# ConverterBoard.net
KiCad netlist of a schematic drawn in EAGLE
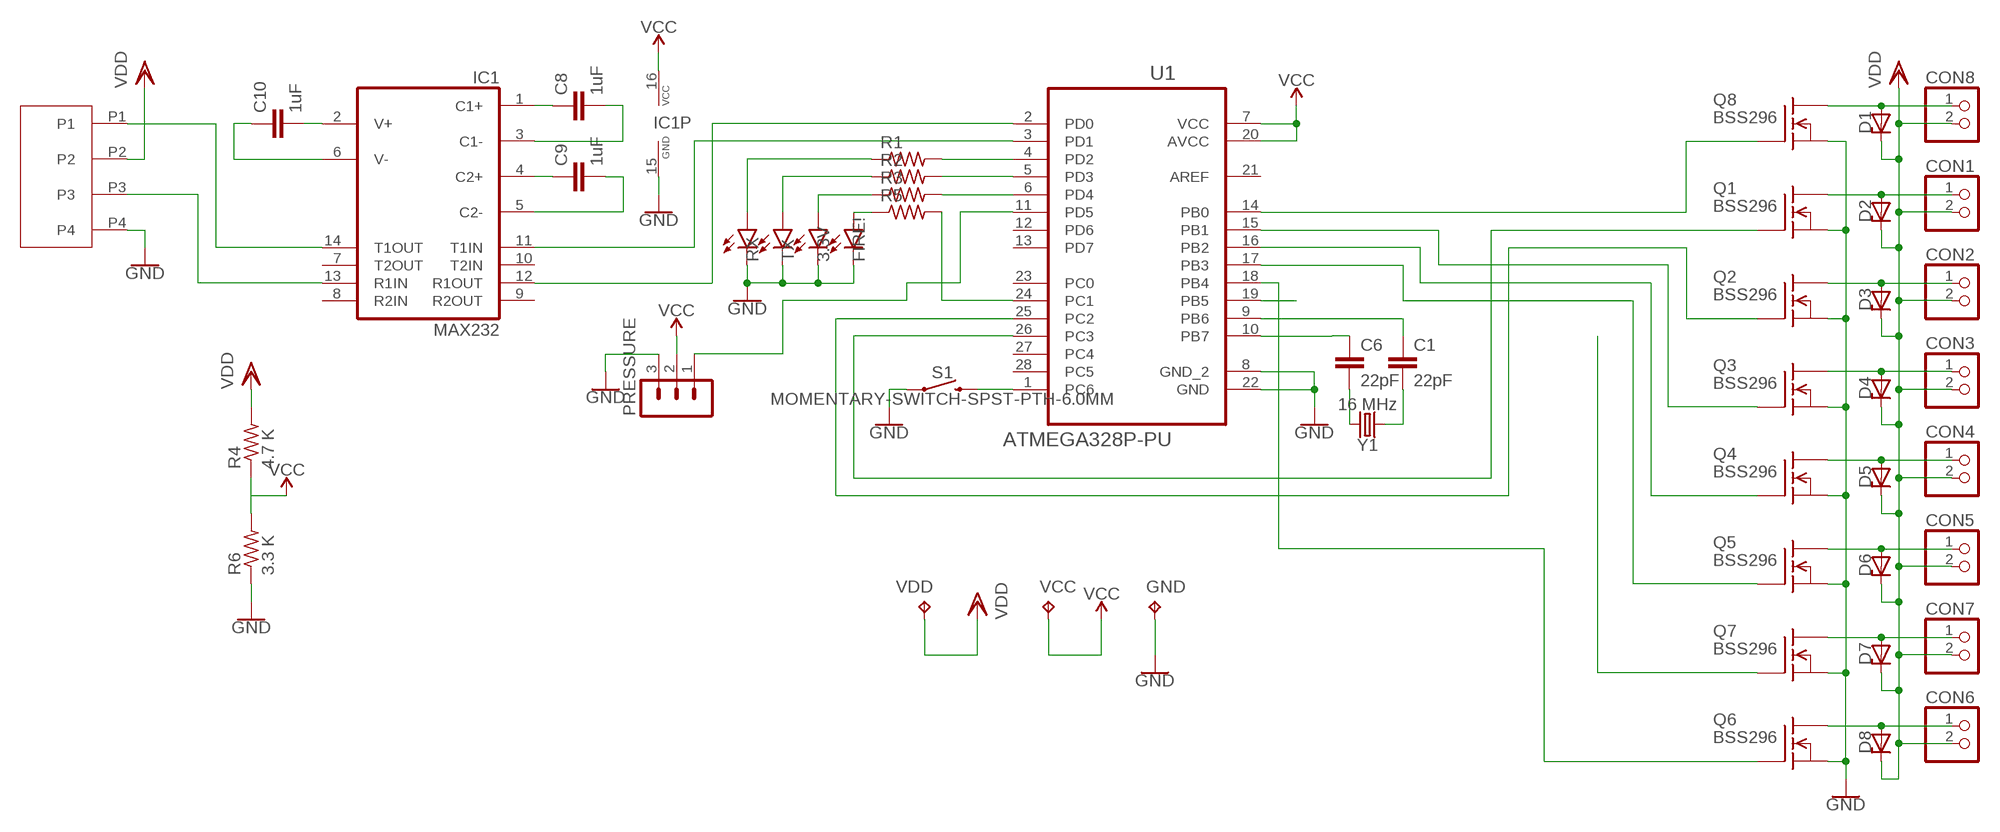
[diagram p0: schematic, sheet 1]

(export (version "E")
  (design (tool "Eeschema 10.0.6"))
  (components
    (comp (ref "3.3V")
      (value "BLUE")
      (footprint "eagle-import:LED-0603")
      (libsource (lib "eagle-import") (part "LED-BLUE0603"))
    )
    (comp (ref "C1")
      (value "22pF")
      (footprint "eagle-import:0603")
      (libsource (lib "eagle-import") (part "470PF-0603-50V-5%"))
    )
    (comp (ref "C6")
      (value "22pF")
      (footprint "eagle-import:0603")
      (libsource (lib "eagle-import") (part "470PF-0603-50V-5%"))
    )
    (comp (ref "C8")
      (value "1uF")
      (footprint "eagle-import:0603")
      (libsource (lib "eagle-import") (part "470PF-0603-50V-5%"))
    )
    (comp (ref "C9")
      (value "1uF")
      (footprint "eagle-import:0603")
      (libsource (lib "eagle-import") (part "470PF-0603-50V-5%"))
    )
    (comp (ref "C10")
      (value "1uF")
      (footprint "eagle-import:0603")
      (libsource (lib "eagle-import") (part "470PF-0603-50V-5%"))
    )
    (comp (ref "CON1")
      (value "PINHD-1X2")
      (footprint "eagle-import:1X02")
      (libsource (lib "eagle-import") (part "PINHD-1X2"))
    )
    (comp (ref "CON2")
      (value "PINHD-1X2")
      (footprint "eagle-import:1X02")
      (libsource (lib "eagle-import") (part "PINHD-1X2"))
    )
    (comp (ref "CON3")
      (value "PINHD-1X2")
      (footprint "eagle-import:1X02")
      (libsource (lib "eagle-import") (part "PINHD-1X2"))
    )
    (comp (ref "CON4")
      (value "PINHD-1X2")
      (footprint "eagle-import:1X02")
      (libsource (lib "eagle-import") (part "PINHD-1X2"))
    )
    (comp (ref "CON5")
      (value "PINHD-1X2")
      (footprint "eagle-import:1X02")
      (libsource (lib "eagle-import") (part "PINHD-1X2"))
    )
    (comp (ref "CON6")
      (value "PINHD-1X2")
      (footprint "eagle-import:1X02")
      (libsource (lib "eagle-import") (part "PINHD-1X2"))
    )
    (comp (ref "CON7")
      (value "PINHD-1X2")
      (footprint "eagle-import:1X02")
      (libsource (lib "eagle-import") (part "PINHD-1X2"))
    )
    (comp (ref "CON8")
      (value "PINHD-1X2")
      (footprint "eagle-import:1X02")
      (libsource (lib "eagle-import") (part "PINHD-1X2"))
    )
    (comp (ref "D1")
      (value "BZX90")
      (footprint "eagle-import:DO34Z7")
      (libsource (lib "eagle-import") (part "BZX90"))
    )
    (comp (ref "D2")
      (value "BZX90")
      (footprint "eagle-import:DO34Z7")
      (libsource (lib "eagle-import") (part "BZX90"))
    )
    (comp (ref "D3")
      (value "BZX90")
      (footprint "eagle-import:DO34Z7")
      (libsource (lib "eagle-import") (part "BZX90"))
    )
    (comp (ref "D4")
      (value "BZX90")
      (footprint "eagle-import:DO34Z7")
      (libsource (lib "eagle-import") (part "BZX90"))
    )
    (comp (ref "D5")
      (value "BZX90")
      (footprint "eagle-import:DO34Z7")
      (libsource (lib "eagle-import") (part "BZX90"))
    )
    (comp (ref "D6")
      (value "BZX90")
      (footprint "eagle-import:DO34Z7")
      (libsource (lib "eagle-import") (part "BZX90"))
    )
    (comp (ref "D7")
      (value "BZX90")
      (footprint "eagle-import:DO34Z7")
      (libsource (lib "eagle-import") (part "BZX90"))
    )
    (comp (ref "D8")
      (value "BZX90")
      (footprint "eagle-import:DO34Z7")
      (libsource (lib "eagle-import") (part "BZX90"))
    )
    (comp (ref "FIRE!")
      (value "BLUE")
      (footprint "eagle-import:LED-0603")
      (libsource (lib "eagle-import") (part "LED-BLUE0603"))
    )
    (comp (ref "GND")
      (value "TPTP11R")
      (footprint "eagle-import:TP11R")
      (libsource (lib "eagle-import") (part "TPTP11R"))
    )
    (comp (ref "IC1")
      (value "MAX232")
      (footprint "eagle-import:DIL16")
      (fields (field (name "MF") "MAXIM") (field (name "MPN") "MAX232ACPE+"))
      (libsource (lib "eagle-import") (part "MAX232"))
    )
    (comp (ref "PRESSURE")
      (value "MA03-1")
      (footprint "eagle-import:MA03-1")
      (libsource (lib "eagle-import") (part "MA03-1"))
    )
    (comp (ref "Q1")
      (value "BSS296")
      (footprint "eagle-import:TO92")
      (libsource (lib "eagle-import") (part "BSS296"))
    )
    (comp (ref "Q2")
      (value "BSS296")
      (footprint "eagle-import:TO92")
      (libsource (lib "eagle-import") (part "BSS296"))
    )
    (comp (ref "Q3")
      (value "BSS296")
      (footprint "eagle-import:TO92")
      (libsource (lib "eagle-import") (part "BSS296"))
    )
    (comp (ref "Q4")
      (value "BSS296")
      (footprint "eagle-import:TO92")
      (libsource (lib "eagle-import") (part "BSS296"))
    )
    (comp (ref "Q5")
      (value "BSS296")
      (footprint "eagle-import:TO92")
      (libsource (lib "eagle-import") (part "BSS296"))
    )
    (comp (ref "Q6")
      (value "BSS296")
      (footprint "eagle-import:TO92")
      (libsource (lib "eagle-import") (part "BSS296"))
    )
    (comp (ref "Q7")
      (value "BSS296")
      (footprint "eagle-import:TO92")
      (libsource (lib "eagle-import") (part "BSS296"))
    )
    (comp (ref "Q8")
      (value "BSS296")
      (footprint "eagle-import:TO92")
      (libsource (lib "eagle-import") (part "BSS296"))
    )
    (comp (ref "R1")
      (value "R-US_0204/2V")
      (footprint "eagle-import:0204V")
      (libsource (lib "eagle-import") (part "R-US_0204/2V"))
    )
    (comp (ref "R2")
      (value "R-US_0204/2V")
      (footprint "eagle-import:0204V")
      (libsource (lib "eagle-import") (part "R-US_0204/2V"))
    )
    (comp (ref "R3")
      (value "R-US_0204/2V")
      (footprint "eagle-import:0204V")
      (libsource (lib "eagle-import") (part "R-US_0204/2V"))
    )
    (comp (ref "R4")
      (value "4.7 K")
      (footprint "eagle-import:0204V")
      (libsource (lib "eagle-import") (part "R-US_0204/2V"))
    )
    (comp (ref "R5")
      (value "R-US_0204/2V")
      (footprint "eagle-import:0204V")
      (libsource (lib "eagle-import") (part "R-US_0204/2V"))
    )
    (comp (ref "R6")
      (value "3.3 K")
      (footprint "eagle-import:0204V")
      (libsource (lib "eagle-import") (part "R-US_0204/2V"))
    )
    (comp (ref "RX")
      (value "BLUE")
      (footprint "eagle-import:LED-0603")
      (libsource (lib "eagle-import") (part "LED-BLUE0603"))
    )
    (comp (ref "S1")
      (value "MOMENTARY-SWITCH-SPST-PTH-6.0MM")
      (footprint "eagle-import:TACTILE_SWITCH_PTH_6.0MM")
      (libsource (lib "eagle-import") (part "MOMENTARY-SWITCH-SPST-PTH-6.0MM"))
    )
    (comp (ref "TX")
      (value "BLUE")
      (footprint "eagle-import:LED-0603")
      (libsource (lib "eagle-import") (part "LED-BLUE0603"))
    )
    (comp (ref "U$2")
      (value "MINI_FIT_JR_4PIN_VERT")
      (footprint "eagle-import:MINI_FIT_JR_4PIN_VERT")
      (libsource (lib "eagle-import") (part "MINI_FIT_JR_4PIN_VERT"))
    )
    (comp (ref "U1")
      (value "ATMEGA328P-PU")
      (footprint "eagle-import:DIP254P762X457-28")
      (libsource (lib "eagle-import") (part "ATMEGA328P-PU"))
    )
    (comp (ref "VCC")
      (value "TPTP11R")
      (footprint "eagle-import:TP11R")
      (libsource (lib "eagle-import") (part "TPTP11R"))
    )
    (comp (ref "VDD")
      (value "TPTP11R")
      (footprint "eagle-import:TP11R")
      (libsource (lib "eagle-import") (part "TPTP11R"))
    )
    (comp (ref "Y1")
      (value "16 MHz")
      (footprint "eagle-import:HC49U")
      (libsource (lib "eagle-import") (part "CRYSTALPTH-HC49UV"))
    )
  )
  (nets
    (net (code "1") (name "/Q7") (class "Default")
      (node (ref "Q7") (pin "1") (pinfunction "G_1") (pintype "passive"))
      (node (ref "U1") (pin "19") (pinfunction "PB5_19") (pintype "bidirectional"))
    )
    (net (code "2") (name "GND") (class "Default")
      (node (ref "3.3V") (pin "C") (pinfunction "C_C") (pintype "passive"))
      (node (ref "FIRE!") (pin "C") (pinfunction "C_C") (pintype "passive"))
      (node (ref "GND") (pin "TP") (pinfunction "TP_TP") (pintype "input"))
      (node (ref "IC1") (pin "15") (pinfunction "GND_15") (pintype "power_in"))
      (node (ref "PRESSURE") (pin "3") (pinfunction "3_3") (pintype "passive"))
      (node (ref "Q1") (pin "3") (pinfunction "S_3") (pintype "passive"))
      (node (ref "Q2") (pin "3") (pinfunction "S_3") (pintype "passive"))
      (node (ref "Q3") (pin "3") (pinfunction "S_3") (pintype "passive"))
      (node (ref "Q4") (pin "3") (pinfunction "S_3") (pintype "passive"))
      (node (ref "Q5") (pin "3") (pinfunction "S_3") (pintype "passive"))
      (node (ref "Q6") (pin "3") (pinfunction "S_3") (pintype "passive"))
      (node (ref "Q7") (pin "3") (pinfunction "S_3") (pintype "passive"))
      (node (ref "Q8") (pin "3") (pinfunction "S_3") (pintype "passive"))
      (node (ref "R6") (pin "1") (pinfunction "1_1") (pintype "passive"))
      (node (ref "RX") (pin "C") (pinfunction "C_C") (pintype "passive"))
      (node (ref "S1") (pin "1") (pinfunction "1_1") (pintype "passive"))
      (node (ref "TX") (pin "C") (pinfunction "C_C") (pintype "passive"))
      (node (ref "U$2") (pin "P4") (pinfunction "P4_P4") (pintype "bidirectional"))
      (node (ref "U1") (pin "22") (pinfunction "GND_22") (pintype "passive"))
      (node (ref "U1") (pin "8") (pinfunction "GND_2_8") (pintype "passive"))
    )
    (net (code "3") (name "Net-(3.3V-PadA)") (class "Default")
      (node (ref "3.3V") (pin "A") (pinfunction "A_A") (pintype "passive"))
      (node (ref "R3") (pin "1") (pinfunction "1_1") (pintype "passive"))
    )
    (net (code "4") (name "Net-(C1-Pad2)") (class "Default")
      (node (ref "C1") (pin "2") (pinfunction "2_2") (pintype "passive"))
      (node (ref "Y1") (pin "1") (pinfunction "1_1") (pintype "passive"))
    )
    (net (code "5") (name "Net-(C6-Pad2)") (class "Default")
      (node (ref "C6") (pin "2") (pinfunction "2_2") (pintype "passive"))
      (node (ref "Y1") (pin "2") (pinfunction "2_2") (pintype "passive"))
    )
    (net (code "6") (name "Net-(FIRE!-PadA)") (class "Default")
      (node (ref "FIRE!") (pin "A") (pinfunction "A_A") (pintype "passive"))
      (node (ref "R5") (pin "1") (pinfunction "1_1") (pintype "passive"))
    )
    (net (code "7") (name "Net-(IC1A-C1+)") (class "Default")
      (node (ref "C8") (pin "1") (pinfunction "1_1") (pintype "passive"))
      (node (ref "IC1") (pin "1") (pinfunction "C1+_1") (pintype "bidirectional"))
    )
    (net (code "8") (name "Net-(IC1A-C1-)") (class "Default")
      (node (ref "C8") (pin "2") (pinfunction "2_2") (pintype "passive"))
      (node (ref "IC1") (pin "3") (pinfunction "C1-_3") (pintype "bidirectional"))
    )
    (net (code "9") (name "Net-(IC1A-C2+)") (class "Default")
      (node (ref "C9") (pin "1") (pinfunction "1_1") (pintype "passive"))
      (node (ref "IC1") (pin "4") (pinfunction "C2+_4") (pintype "bidirectional"))
    )
    (net (code "10") (name "Net-(IC1A-C2-)") (class "Default")
      (node (ref "C9") (pin "2") (pinfunction "2_2") (pintype "passive"))
      (node (ref "IC1") (pin "5") (pinfunction "C2-_5") (pintype "bidirectional"))
    )
    (net (code "11") (name "Net-(IC1A-R1IN)") (class "Default")
      (node (ref "IC1") (pin "13") (pinfunction "R1IN_13") (pintype "input"))
      (node (ref "U$2") (pin "P3") (pinfunction "P3_P3") (pintype "bidirectional"))
    )
    (net (code "12") (name "Net-(IC1A-R1OUT)") (class "Default")
      (node (ref "IC1") (pin "12") (pinfunction "R1OUT_12") (pintype "output"))
      (node (ref "U1") (pin "2") (pinfunction "PD0_2") (pintype "bidirectional"))
    )
    (net (code "13") (name "Net-(IC1A-T1IN)") (class "Default")
      (node (ref "IC1") (pin "11") (pinfunction "T1IN_11") (pintype "input"))
      (node (ref "U1") (pin "3") (pinfunction "PD1_3") (pintype "bidirectional"))
    )
    (net (code "14") (name "Net-(IC1A-T1OUT)") (class "Default")
      (node (ref "IC1") (pin "14") (pinfunction "T1OUT_14") (pintype "output"))
      (node (ref "U$2") (pin "P1") (pinfunction "P1_P1") (pintype "bidirectional"))
    )
    (net (code "15") (name "Net-(IC1A-V+)") (class "Default")
      (node (ref "C10") (pin "2") (pinfunction "2_2") (pintype "passive"))
      (node (ref "IC1") (pin "2") (pinfunction "V+_2") (pintype "bidirectional"))
    )
    (net (code "16") (name "Net-(IC1A-V-)") (class "Default")
      (node (ref "C10") (pin "1") (pinfunction "1_1") (pintype "passive"))
      (node (ref "IC1") (pin "6") (pinfunction "V-_6") (pintype "bidirectional"))
    )
    (net (code "17") (name "Net-(Q1-D)") (class "Default")
      (node (ref "CON1") (pin "1") (pinfunction "1_1") (pintype "passive"))
      (node (ref "D2") (pin "A") (pinfunction "A_A") (pintype "passive"))
      (node (ref "Q1") (pin "2") (pinfunction "D_2") (pintype "passive"))
    )
    (net (code "18") (name "Net-(Q1-G)") (class "Default")
      (node (ref "Q1") (pin "1") (pinfunction "G_1") (pintype "passive"))
      (node (ref "U1") (pin "26") (pinfunction "PC3_26") (pintype "bidirectional"))
    )
    (net (code "19") (name "Net-(Q2-D)") (class "Default")
      (node (ref "CON2") (pin "1") (pinfunction "1_1") (pintype "passive"))
      (node (ref "D3") (pin "A") (pinfunction "A_A") (pintype "passive"))
      (node (ref "Q2") (pin "2") (pinfunction "D_2") (pintype "passive"))
    )
    (net (code "20") (name "Net-(Q2-G)") (class "Default")
      (node (ref "Q2") (pin "1") (pinfunction "G_1") (pintype "passive"))
      (node (ref "U1") (pin "25") (pinfunction "PC2_25") (pintype "bidirectional"))
    )
    (net (code "21") (name "Net-(Q3-D)") (class "Default")
      (node (ref "CON3") (pin "1") (pinfunction "1_1") (pintype "passive"))
      (node (ref "D4") (pin "A") (pinfunction "A_A") (pintype "passive"))
      (node (ref "Q3") (pin "2") (pinfunction "D_2") (pintype "passive"))
    )
    (net (code "22") (name "Net-(Q3-G)") (class "Default")
      (node (ref "Q3") (pin "1") (pinfunction "G_1") (pintype "passive"))
      (node (ref "U1") (pin "15") (pinfunction "PB1_15") (pintype "bidirectional"))
    )
    (net (code "23") (name "Net-(Q4-D)") (class "Default")
      (node (ref "CON4") (pin "1") (pinfunction "1_1") (pintype "passive"))
      (node (ref "D5") (pin "A") (pinfunction "A_A") (pintype "passive"))
      (node (ref "Q4") (pin "2") (pinfunction "D_2") (pintype "passive"))
    )
    (net (code "24") (name "Net-(Q4-G)") (class "Default")
      (node (ref "Q4") (pin "1") (pinfunction "G_1") (pintype "passive"))
      (node (ref "U1") (pin "16") (pinfunction "PB2_16") (pintype "bidirectional"))
    )
    (net (code "25") (name "Net-(Q5-D)") (class "Default")
      (node (ref "CON5") (pin "1") (pinfunction "1_1") (pintype "passive"))
      (node (ref "D6") (pin "A") (pinfunction "A_A") (pintype "passive"))
      (node (ref "Q5") (pin "2") (pinfunction "D_2") (pintype "passive"))
    )
    (net (code "26") (name "Net-(Q5-G)") (class "Default")
      (node (ref "Q5") (pin "1") (pinfunction "G_1") (pintype "passive"))
      (node (ref "U1") (pin "17") (pinfunction "PB3_17") (pintype "bidirectional"))
    )
    (net (code "27") (name "Net-(Q6-D)") (class "Default")
      (node (ref "CON6") (pin "1") (pinfunction "1_1") (pintype "passive"))
      (node (ref "D8") (pin "A") (pinfunction "A_A") (pintype "passive"))
      (node (ref "Q6") (pin "2") (pinfunction "D_2") (pintype "passive"))
    )
    (net (code "28") (name "Net-(Q6-G)") (class "Default")
      (node (ref "Q6") (pin "1") (pinfunction "G_1") (pintype "passive"))
      (node (ref "U1") (pin "18") (pinfunction "PB4_18") (pintype "bidirectional"))
    )
    (net (code "29") (name "Net-(Q7-D)") (class "Default")
      (node (ref "CON7") (pin "1") (pinfunction "1_1") (pintype "passive"))
      (node (ref "D7") (pin "A") (pinfunction "A_A") (pintype "passive"))
      (node (ref "Q7") (pin "2") (pinfunction "D_2") (pintype "passive"))
    )
    (net (code "30") (name "Net-(Q8-D)") (class "Default")
      (node (ref "CON8") (pin "1") (pinfunction "1_1") (pintype "passive"))
      (node (ref "D1") (pin "A") (pinfunction "A_A") (pintype "passive"))
      (node (ref "Q8") (pin "2") (pinfunction "D_2") (pintype "passive"))
    )
    (net (code "31") (name "Net-(Q8-G)") (class "Default")
      (node (ref "Q8") (pin "1") (pinfunction "G_1") (pintype "passive"))
      (node (ref "U1") (pin "14") (pinfunction "PB0_14") (pintype "bidirectional"))
    )
    (net (code "32") (name "Net-(R1-Pad1)") (class "Default")
      (node (ref "R1") (pin "1") (pinfunction "1_1") (pintype "passive"))
      (node (ref "RX") (pin "A") (pinfunction "A_A") (pintype "passive"))
    )
    (net (code "33") (name "Net-(R2-Pad1)") (class "Default")
      (node (ref "R2") (pin "1") (pinfunction "1_1") (pintype "passive"))
      (node (ref "TX") (pin "A") (pinfunction "A_A") (pintype "passive"))
    )
    (net (code "34") (name "Net-(R4-Pad1)") (class "Default")
      (node (ref "R4") (pin "1") (pinfunction "1_1") (pintype "passive"))
      (node (ref "R6") (pin "2") (pinfunction "2_2") (pintype "passive"))
    )
    (net (code "35") (name "Net-(S1-2)") (class "Default")
      (node (ref "S1") (pin "3") (pinfunction "2_3") (pintype "passive"))
      (node (ref "U1") (pin "1") (pinfunction "PC6_1") (pintype "bidirectional"))
    )
    (net (code "36") (name "Net-(U1-PB6)") (class "Default")
      (node (ref "C1") (pin "1") (pinfunction "1_1") (pintype "passive"))
      (node (ref "U1") (pin "9") (pinfunction "PB6_9") (pintype "bidirectional"))
    )
    (net (code "37") (name "Net-(U1-PB7)") (class "Default")
      (node (ref "C6") (pin "1") (pinfunction "1_1") (pintype "passive"))
      (node (ref "U1") (pin "10") (pinfunction "PB7_10") (pintype "bidirectional"))
    )
    (net (code "38") (name "Net-(U1-PC1)") (class "Default")
      (node (ref "R5") (pin "2") (pinfunction "2_2") (pintype "passive"))
      (node (ref "U1") (pin "24") (pinfunction "PC1_24") (pintype "bidirectional"))
    )
    (net (code "39") (name "Net-(U1-PD2)") (class "Default")
      (node (ref "R1") (pin "2") (pinfunction "2_2") (pintype "passive"))
      (node (ref "U1") (pin "4") (pinfunction "PD2_4") (pintype "bidirectional"))
    )
    (net (code "40") (name "Net-(U1-PD3)") (class "Default")
      (node (ref "R2") (pin "2") (pinfunction "2_2") (pintype "passive"))
      (node (ref "U1") (pin "5") (pinfunction "PD3_5") (pintype "bidirectional"))
    )
    (net (code "41") (name "Net-(U1-PD4)") (class "Default")
      (node (ref "R3") (pin "2") (pinfunction "2_2") (pintype "passive"))
      (node (ref "U1") (pin "6") (pinfunction "PD4_6") (pintype "bidirectional"))
    )
    (net (code "42") (name "Net-(U1-PD5)") (class "Default")
      (node (ref "PRESSURE") (pin "1") (pinfunction "1_1") (pintype "passive"))
      (node (ref "U1") (pin "11") (pinfunction "PD5_11") (pintype "bidirectional"))
    )
    (net (code "43") (name "VCC") (class "Default")
      (node (ref "IC1") (pin "16") (pinfunction "VCC_16") (pintype "power_in"))
      (node (ref "PRESSURE") (pin "2") (pinfunction "2_2") (pintype "passive"))
      (node (ref "U1") (pin "20") (pinfunction "AVCC_20") (pintype "power_in"))
      (node (ref "U1") (pin "7") (pinfunction "VCC_7") (pintype "power_in"))
      (node (ref "VCC") (pin "TP") (pinfunction "TP_TP") (pintype "input"))
    )
    (net (code "44") (name "VDD") (class "Default")
      (node (ref "CON1") (pin "2") (pinfunction "2_2") (pintype "passive"))
      (node (ref "CON2") (pin "2") (pinfunction "2_2") (pintype "passive"))
      (node (ref "CON3") (pin "2") (pinfunction "2_2") (pintype "passive"))
      (node (ref "CON4") (pin "2") (pinfunction "2_2") (pintype "passive"))
      (node (ref "CON5") (pin "2") (pinfunction "2_2") (pintype "passive"))
      (node (ref "CON6") (pin "2") (pinfunction "2_2") (pintype "passive"))
      (node (ref "CON7") (pin "2") (pinfunction "2_2") (pintype "passive"))
      (node (ref "CON8") (pin "2") (pinfunction "2_2") (pintype "passive"))
      (node (ref "D1") (pin "C") (pinfunction "C_C") (pintype "passive"))
      (node (ref "D2") (pin "C") (pinfunction "C_C") (pintype "passive"))
      (node (ref "D3") (pin "C") (pinfunction "C_C") (pintype "passive"))
      (node (ref "D4") (pin "C") (pinfunction "C_C") (pintype "passive"))
      (node (ref "D5") (pin "C") (pinfunction "C_C") (pintype "passive"))
      (node (ref "D6") (pin "C") (pinfunction "C_C") (pintype "passive"))
      (node (ref "D7") (pin "C") (pinfunction "C_C") (pintype "passive"))
      (node (ref "D8") (pin "C") (pinfunction "C_C") (pintype "passive"))
      (node (ref "R4") (pin "2") (pinfunction "2_2") (pintype "passive"))
      (node (ref "U$2") (pin "P2") (pinfunction "P2_P2") (pintype "bidirectional"))
      (node (ref "VDD") (pin "TP") (pinfunction "TP_TP") (pintype "input"))
    )
    (net (code "45") (name "unconnected-(IC1A-R2IN-Pad8)") (class "Default")
      (node (ref "IC1") (pin "8") (pinfunction "R2IN_8") (pintype "input"))
    )
    (net (code "46") (name "unconnected-(IC1A-R2OUT-Pad9)") (class "Default")
      (node (ref "IC1") (pin "9") (pinfunction "R2OUT_9") (pintype "output"))
    )
    (net (code "47") (name "unconnected-(IC1A-T2IN-Pad10)") (class "Default")
      (node (ref "IC1") (pin "10") (pinfunction "T2IN_10") (pintype "input"))
    )
    (net (code "48") (name "unconnected-(IC1A-T2OUT-Pad7)") (class "Default")
      (node (ref "IC1") (pin "7") (pinfunction "T2OUT_7") (pintype "output"))
    )
    (net (code "49") (name "unconnected-(U1-AREF-Pad21)") (class "Default")
      (node (ref "U1") (pin "21") (pinfunction "AREF_21") (pintype "input"))
    )
    (net (code "50") (name "unconnected-(U1-PC0-Pad23)") (class "Default")
      (node (ref "U1") (pin "23") (pinfunction "PC0_23") (pintype "bidirectional"))
    )
    (net (code "51") (name "unconnected-(U1-PC4-Pad27)") (class "Default")
      (node (ref "U1") (pin "27") (pinfunction "PC4_27") (pintype "bidirectional"))
    )
    (net (code "52") (name "unconnected-(U1-PC5-Pad28)") (class "Default")
      (node (ref "U1") (pin "28") (pinfunction "PC5_28") (pintype "bidirectional"))
    )
    (net (code "53") (name "unconnected-(U1-PD6-Pad12)") (class "Default")
      (node (ref "U1") (pin "12") (pinfunction "PD6_12") (pintype "bidirectional"))
    )
    (net (code "54") (name "unconnected-(U1-PD7-Pad13)") (class "Default")
      (node (ref "U1") (pin "13") (pinfunction "PD7_13") (pintype "bidirectional"))
    )
  )
)
